# UpLiftDesk.net
KiCad netlist of a schematic drawn in EAGLE
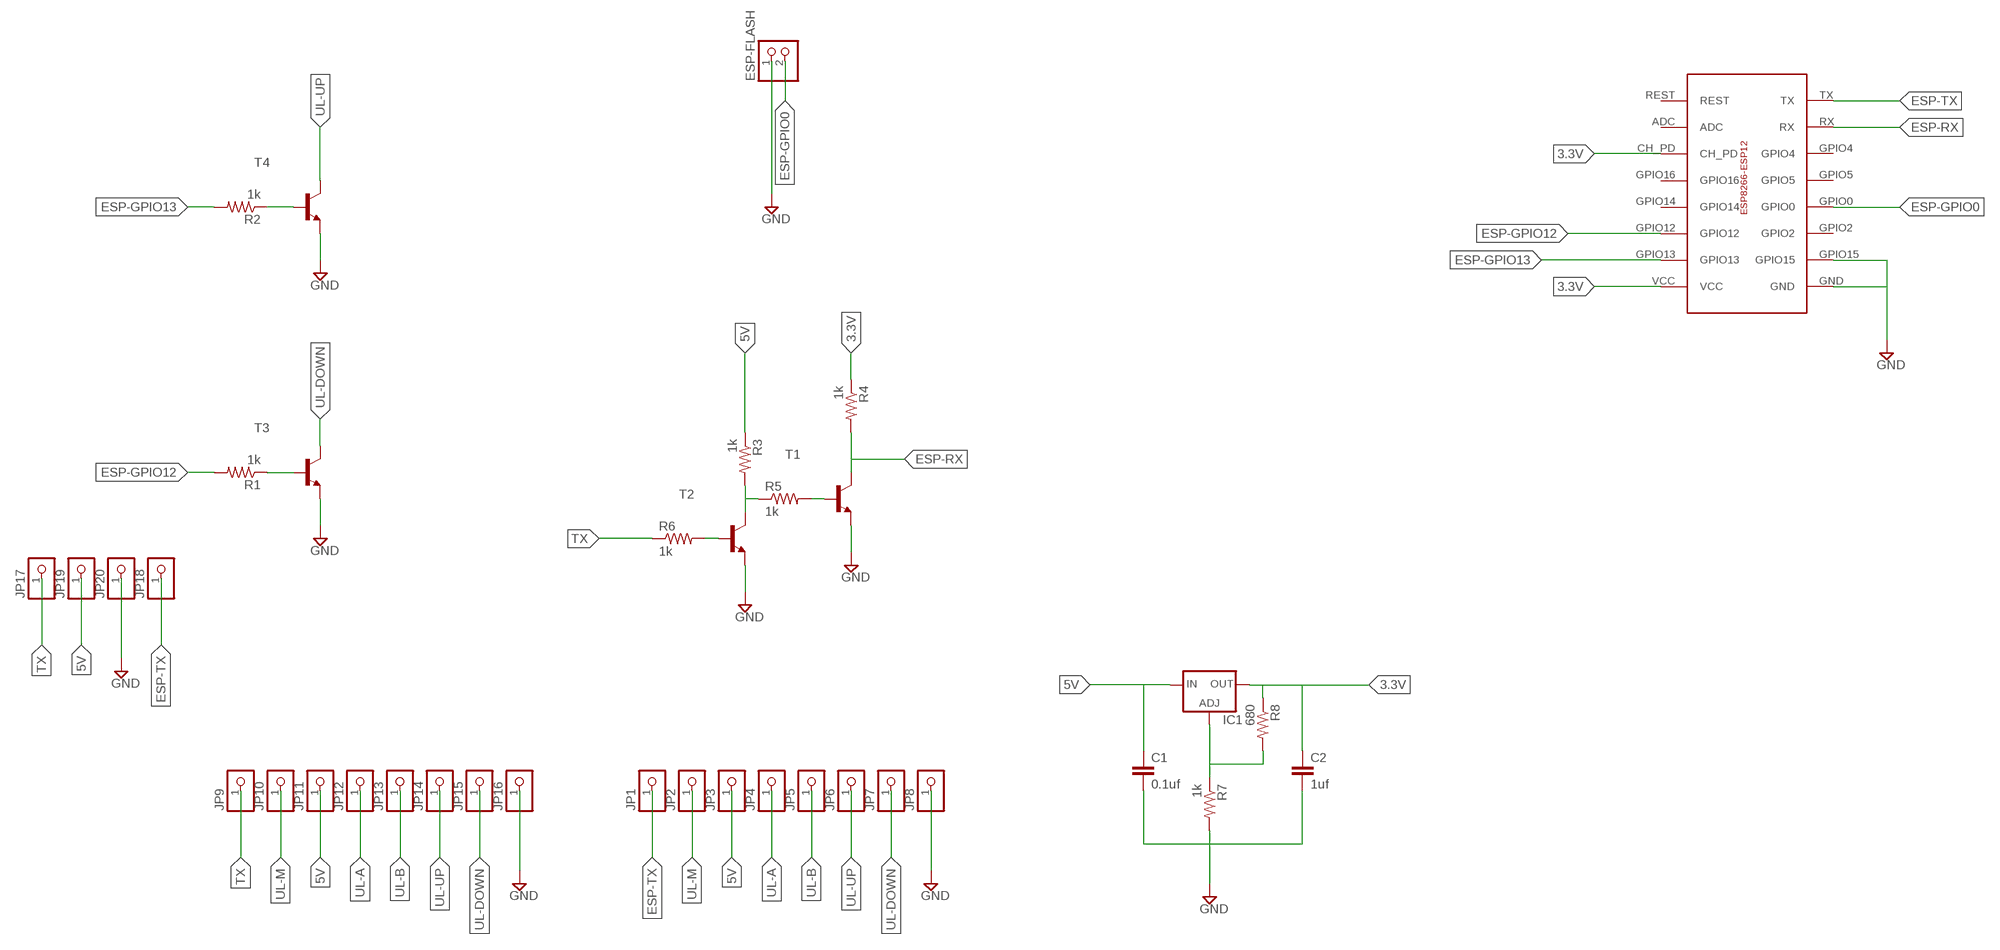
[diagram p0: schematic, sheet 1]

(export (version "E")
  (design (tool "Eeschema 10.0.6"))
  (components
    (comp (ref "C1")
      (value "0.1uf")
      (footprint "eagle-import:C2.5-2")
      (libsource (lib "eagle-import") (part "C2.5/2"))
    )
    (comp (ref "C2")
      (value "1uf")
      (footprint "eagle-import:C2.5-2")
      (libsource (lib "eagle-import") (part "C2.5/2"))
    )
    (comp (ref "ESP-FLASH")
      (value "PINHD-1X2")
      (footprint "eagle-import:1X02")
      (libsource (lib "eagle-import") (part "PINHD-1X2"))
    )
    (comp (ref "IC1")
      (value "LM317TS")
      (footprint "eagle-import:317TS")
      (libsource (lib "eagle-import") (part "LM317TS"))
    )
    (comp (ref "JP1")
      (value "PINHD-1X1")
      (footprint "eagle-import:1X01")
      (libsource (lib "eagle-import") (part "PINHD-1X1"))
    )
    (comp (ref "JP2")
      (value "PINHD-1X1")
      (footprint "eagle-import:1X01")
      (libsource (lib "eagle-import") (part "PINHD-1X1"))
    )
    (comp (ref "JP3")
      (value "PINHD-1X1")
      (footprint "eagle-import:1X01")
      (libsource (lib "eagle-import") (part "PINHD-1X1"))
    )
    (comp (ref "JP4")
      (value "PINHD-1X1")
      (footprint "eagle-import:1X01")
      (libsource (lib "eagle-import") (part "PINHD-1X1"))
    )
    (comp (ref "JP5")
      (value "PINHD-1X1")
      (footprint "eagle-import:1X01")
      (libsource (lib "eagle-import") (part "PINHD-1X1"))
    )
    (comp (ref "JP6")
      (value "PINHD-1X1")
      (footprint "eagle-import:1X01")
      (libsource (lib "eagle-import") (part "PINHD-1X1"))
    )
    (comp (ref "JP7")
      (value "PINHD-1X1")
      (footprint "eagle-import:1X01")
      (libsource (lib "eagle-import") (part "PINHD-1X1"))
    )
    (comp (ref "JP8")
      (value "PINHD-1X1")
      (footprint "eagle-import:1X01")
      (libsource (lib "eagle-import") (part "PINHD-1X1"))
    )
    (comp (ref "JP9")
      (value "PINHD-1X1")
      (footprint "eagle-import:1X01")
      (libsource (lib "eagle-import") (part "PINHD-1X1"))
    )
    (comp (ref "JP10")
      (value "PINHD-1X1")
      (footprint "eagle-import:1X01")
      (libsource (lib "eagle-import") (part "PINHD-1X1"))
    )
    (comp (ref "JP11")
      (value "PINHD-1X1")
      (footprint "eagle-import:1X01")
      (libsource (lib "eagle-import") (part "PINHD-1X1"))
    )
    (comp (ref "JP12")
      (value "PINHD-1X1")
      (footprint "eagle-import:1X01")
      (libsource (lib "eagle-import") (part "PINHD-1X1"))
    )
    (comp (ref "JP13")
      (value "PINHD-1X1")
      (footprint "eagle-import:1X01")
      (libsource (lib "eagle-import") (part "PINHD-1X1"))
    )
    (comp (ref "JP14")
      (value "PINHD-1X1")
      (footprint "eagle-import:1X01")
      (libsource (lib "eagle-import") (part "PINHD-1X1"))
    )
    (comp (ref "JP15")
      (value "PINHD-1X1")
      (footprint "eagle-import:1X01")
      (libsource (lib "eagle-import") (part "PINHD-1X1"))
    )
    (comp (ref "JP16")
      (value "PINHD-1X1")
      (footprint "eagle-import:1X01")
      (libsource (lib "eagle-import") (part "PINHD-1X1"))
    )
    (comp (ref "JP17")
      (value "PINHD-1X1")
      (footprint "eagle-import:1X01")
      (libsource (lib "eagle-import") (part "PINHD-1X1"))
    )
    (comp (ref "JP18")
      (value "PINHD-1X1")
      (footprint "eagle-import:1X01")
      (libsource (lib "eagle-import") (part "PINHD-1X1"))
    )
    (comp (ref "JP19")
      (value "PINHD-1X1")
      (footprint "eagle-import:1X01")
      (libsource (lib "eagle-import") (part "PINHD-1X1"))
    )
    (comp (ref "JP20")
      (value "PINHD-1X1")
      (footprint "eagle-import:1X01")
      (libsource (lib "eagle-import") (part "PINHD-1X1"))
    )
    (comp (ref "R1")
      (value "1k")
      (footprint "eagle-import:0204_7")
      (libsource (lib "eagle-import") (part "R-US_0204/7"))
    )
    (comp (ref "R2")
      (value "1k")
      (footprint "eagle-import:0204_7")
      (libsource (lib "eagle-import") (part "R-US_0204/7"))
    )
    (comp (ref "R3")
      (value "1k")
      (footprint "eagle-import:0204_7")
      (libsource (lib "eagle-import") (part "R-US_0204/7"))
    )
    (comp (ref "R4")
      (value "1k")
      (footprint "eagle-import:0204_7")
      (libsource (lib "eagle-import") (part "R-US_0204/7"))
    )
    (comp (ref "R5")
      (value "1k")
      (footprint "eagle-import:0204_7")
      (libsource (lib "eagle-import") (part "R-US_0204/7"))
    )
    (comp (ref "R6")
      (value "1k")
      (footprint "eagle-import:0204_7")
      (libsource (lib "eagle-import") (part "R-US_0204/7"))
    )
    (comp (ref "R7")
      (value "1k")
      (footprint "eagle-import:0204_7")
      (libsource (lib "eagle-import") (part "R-US_0204/7"))
    )
    (comp (ref "R8")
      (value "680")
      (footprint "eagle-import:0204_7")
      (libsource (lib "eagle-import") (part "R-US_0204/7"))
    )
    (comp (ref "T1")
      (value "-NPN-TO92-EBC")
      (footprint "eagle-import:TO92-EBC")
      (libsource (lib "eagle-import") (part "-NPN-TO92-EBC"))
    )
    (comp (ref "T2")
      (value "-NPN-TO92-EBC")
      (footprint "eagle-import:TO92-EBC")
      (libsource (lib "eagle-import") (part "-NPN-TO92-EBC"))
    )
    (comp (ref "T3")
      (value "-NPN-TO92-EBC")
      (footprint "eagle-import:TO92-EBC")
      (libsource (lib "eagle-import") (part "-NPN-TO92-EBC"))
    )
    (comp (ref "T4")
      (value "-NPN-TO92-EBC")
      (footprint "eagle-import:TO92-EBC")
      (libsource (lib "eagle-import") (part "-NPN-TO92-EBC"))
    )
    (comp (ref "U$2")
      (value "ESP-12-THROUGH")
      (footprint "eagle-import:ESP-12-THROUGH")
      (libsource (lib "eagle-import") (part "ESP-12-THROUGH"))
    )
  )
  (nets
    (net (code "1") (name "3.3V") (class "Default")
      (node (ref "C2") (pin "1") (pinfunction "1_1") (pintype "passive"))
      (node (ref "IC1") (pin "2") (pinfunction "OUT_2") (pintype "passive"))
      (node (ref "R4") (pin "1") (pinfunction "1_1") (pintype "passive"))
      (node (ref "R8") (pin "1") (pinfunction "1_1") (pintype "passive"))
      (node (ref "U$2") (pin "CH_PD") (pinfunction "CH_PD_CH_PD") (pintype "bidirectional"))
      (node (ref "U$2") (pin "VCC") (pinfunction "VCC_VCC") (pintype "bidirectional"))
    )
    (net (code "2") (name "5V") (class "Default")
      (node (ref "C1") (pin "1") (pinfunction "1_1") (pintype "passive"))
      (node (ref "IC1") (pin "3") (pinfunction "IN_3") (pintype "input"))
      (node (ref "JP11") (pin "1") (pinfunction "1_1") (pintype "passive"))
      (node (ref "JP19") (pin "1") (pinfunction "1_1") (pintype "passive"))
      (node (ref "JP3") (pin "1") (pinfunction "1_1") (pintype "passive"))
      (node (ref "R3") (pin "1") (pinfunction "1_1") (pintype "passive"))
    )
    (net (code "3") (name "ESP-GPIO0") (class "Default")
      (node (ref "ESP-FLASH") (pin "2") (pinfunction "2_2") (pintype "passive"))
      (node (ref "U$2") (pin "GPIO0") (pinfunction "GPIO0_GPIO0") (pintype "bidirectional"))
    )
    (net (code "4") (name "ESP-GPIO12") (class "Default")
      (node (ref "R1") (pin "2") (pinfunction "2_2") (pintype "passive"))
      (node (ref "U$2") (pin "GPIO12") (pinfunction "GPIO12_GPIO12") (pintype "bidirectional"))
    )
    (net (code "5") (name "ESP-GPIO13") (class "Default")
      (node (ref "R2") (pin "2") (pinfunction "2_2") (pintype "passive"))
      (node (ref "U$2") (pin "GPIO13") (pinfunction "GPIO13_GPIO13") (pintype "bidirectional"))
    )
    (net (code "6") (name "ESP-RX") (class "Default")
      (node (ref "R4") (pin "2") (pinfunction "2_2") (pintype "passive"))
      (node (ref "T1") (pin "C") (pinfunction "C_C") (pintype "passive"))
      (node (ref "U$2") (pin "RX") (pinfunction "RX_RX") (pintype "bidirectional"))
    )
    (net (code "7") (name "ESP-TX") (class "Default")
      (node (ref "JP1") (pin "1") (pinfunction "1_1") (pintype "passive"))
      (node (ref "JP18") (pin "1") (pinfunction "1_1") (pintype "passive"))
      (node (ref "U$2") (pin "TX") (pinfunction "TX_TX") (pintype "bidirectional"))
    )
    (net (code "8") (name "GND") (class "Default")
      (node (ref "C1") (pin "2") (pinfunction "2_2") (pintype "passive"))
      (node (ref "C2") (pin "2") (pinfunction "2_2") (pintype "passive"))
      (node (ref "ESP-FLASH") (pin "1") (pinfunction "1_1") (pintype "passive"))
      (node (ref "JP16") (pin "1") (pinfunction "1_1") (pintype "passive"))
      (node (ref "JP20") (pin "1") (pinfunction "1_1") (pintype "passive"))
      (node (ref "JP8") (pin "1") (pinfunction "1_1") (pintype "passive"))
      (node (ref "R7") (pin "2") (pinfunction "2_2") (pintype "passive"))
      (node (ref "T1") (pin "E") (pinfunction "E_E") (pintype "passive"))
      (node (ref "T2") (pin "E") (pinfunction "E_E") (pintype "passive"))
      (node (ref "T3") (pin "E") (pinfunction "E_E") (pintype "passive"))
      (node (ref "T4") (pin "E") (pinfunction "E_E") (pintype "passive"))
      (node (ref "U$2") (pin "GND") (pinfunction "GND_GND") (pintype "bidirectional"))
      (node (ref "U$2") (pin "GPIO15") (pinfunction "GPIO15_GPIO15") (pintype "bidirectional"))
    )
    (net (code "9") (name "Net-(IC1-ADJ)") (class "Default")
      (node (ref "IC1") (pin "1") (pinfunction "ADJ_1") (pintype "input"))
      (node (ref "R7") (pin "1") (pinfunction "1_1") (pintype "passive"))
      (node (ref "R8") (pin "2") (pinfunction "2_2") (pintype "passive"))
    )
    (net (code "10") (name "Net-(R1-Pad1)") (class "Default")
      (node (ref "R1") (pin "1") (pinfunction "1_1") (pintype "passive"))
      (node (ref "T3") (pin "B") (pinfunction "B_B") (pintype "passive"))
    )
    (net (code "11") (name "Net-(R2-Pad1)") (class "Default")
      (node (ref "R2") (pin "1") (pinfunction "1_1") (pintype "passive"))
      (node (ref "T4") (pin "B") (pinfunction "B_B") (pintype "passive"))
    )
    (net (code "12") (name "Net-(R3-Pad2)") (class "Default")
      (node (ref "R3") (pin "2") (pinfunction "2_2") (pintype "passive"))
      (node (ref "R5") (pin "1") (pinfunction "1_1") (pintype "passive"))
      (node (ref "T2") (pin "C") (pinfunction "C_C") (pintype "passive"))
    )
    (net (code "13") (name "Net-(R5-Pad2)") (class "Default")
      (node (ref "R5") (pin "2") (pinfunction "2_2") (pintype "passive"))
      (node (ref "T1") (pin "B") (pinfunction "B_B") (pintype "passive"))
    )
    (net (code "14") (name "Net-(R6-Pad2)") (class "Default")
      (node (ref "R6") (pin "2") (pinfunction "2_2") (pintype "passive"))
      (node (ref "T2") (pin "B") (pinfunction "B_B") (pintype "passive"))
    )
    (net (code "15") (name "TX") (class "Default")
      (node (ref "JP17") (pin "1") (pinfunction "1_1") (pintype "passive"))
      (node (ref "JP9") (pin "1") (pinfunction "1_1") (pintype "passive"))
      (node (ref "R6") (pin "1") (pinfunction "1_1") (pintype "passive"))
    )
    (net (code "16") (name "UL-A") (class "Default")
      (node (ref "JP12") (pin "1") (pinfunction "1_1") (pintype "passive"))
      (node (ref "JP4") (pin "1") (pinfunction "1_1") (pintype "passive"))
    )
    (net (code "17") (name "UL-B") (class "Default")
      (node (ref "JP13") (pin "1") (pinfunction "1_1") (pintype "passive"))
      (node (ref "JP5") (pin "1") (pinfunction "1_1") (pintype "passive"))
    )
    (net (code "18") (name "UL-DOWN") (class "Default")
      (node (ref "JP15") (pin "1") (pinfunction "1_1") (pintype "passive"))
      (node (ref "JP7") (pin "1") (pinfunction "1_1") (pintype "passive"))
      (node (ref "T3") (pin "C") (pinfunction "C_C") (pintype "passive"))
    )
    (net (code "19") (name "UL-M") (class "Default")
      (node (ref "JP10") (pin "1") (pinfunction "1_1") (pintype "passive"))
      (node (ref "JP2") (pin "1") (pinfunction "1_1") (pintype "passive"))
    )
    (net (code "20") (name "UL-UP") (class "Default")
      (node (ref "JP14") (pin "1") (pinfunction "1_1") (pintype "passive"))
      (node (ref "JP6") (pin "1") (pinfunction "1_1") (pintype "passive"))
      (node (ref "T4") (pin "C") (pinfunction "C_C") (pintype "passive"))
    )
    (net (code "21") (name "unconnected-(U$2-PadADC)") (class "Default")
      (node (ref "U$2") (pin "ADC") (pinfunction "ADC_ADC") (pintype "bidirectional"))
    )
    (net (code "22") (name "unconnected-(U$2-PadGPIO2)") (class "Default")
      (node (ref "U$2") (pin "GPIO2") (pinfunction "GPIO2_GPIO2") (pintype "bidirectional"))
    )
    (net (code "23") (name "unconnected-(U$2-PadGPIO4)") (class "Default")
      (node (ref "U$2") (pin "GPIO4") (pinfunction "GPIO4_GPIO4") (pintype "bidirectional"))
    )
    (net (code "24") (name "unconnected-(U$2-PadGPIO5)") (class "Default")
      (node (ref "U$2") (pin "GPIO5") (pinfunction "GPIO5_GPIO5") (pintype "bidirectional"))
    )
    (net (code "25") (name "unconnected-(U$2-PadGPIO14)") (class "Default")
      (node (ref "U$2") (pin "GPIO14") (pinfunction "GPIO14_GPIO14") (pintype "bidirectional"))
    )
    (net (code "26") (name "unconnected-(U$2-PadGPIO16)") (class "Default")
      (node (ref "U$2") (pin "GPIO16") (pinfunction "GPIO16_GPIO16") (pintype "bidirectional"))
    )
    (net (code "27") (name "unconnected-(U$2-PadREST)") (class "Default")
      (node (ref "U$2") (pin "REST") (pinfunction "REST_REST") (pintype "bidirectional"))
    )
  )
)
